# blinky_schematic.net
KiCad netlist of a schematic drawn in EAGLE
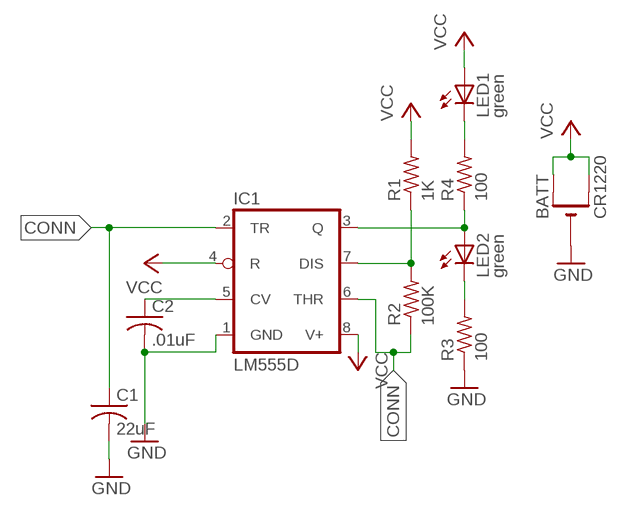
[diagram p0: schematic, sheet 1]

(export (version "E")
  (design (tool "Eeschema 10.0.6"))
  (components
    (comp (ref "BATT")
      (value "CR1220")
      (footprint "eagle-import:CR1220-SMD")
      (fields (field (name "MPN") "3080"))
      (libsource (lib "eagle-import") (part "CR1220SMT"))
    )
    (comp (ref "C1")
      (value "22uF")
      (footprint "eagle-import:C0805")
      (fields (field (name "MPN") "F981A226MSAAS1"))
      (libsource (lib "eagle-import") (part "C-USC0805"))
    )
    (comp (ref "C2")
      (value ".01uF")
      (footprint "eagle-import:C0805")
      (fields (field (name "MPN") "0805PC103KAZ1A"))
      (libsource (lib "eagle-import") (part "C-USC0805"))
    )
    (comp (ref "IC1")
      (value "LM555D")
      (footprint "eagle-import:SO08")
      (fields (field (name "MPN") "1526"))
      (libsource (lib "eagle-import") (part "555DLM"))
    )
    (comp (ref "LED1")
      (value "green")
      (footprint "eagle-import:CHIPLED_0805")
      (fields (field (name "MPN") "5988170107F"))
      (libsource (lib "eagle-import") (part "LEDCHIPLED_0805"))
    )
    (comp (ref "LED2")
      (value "green")
      (footprint "eagle-import:CHIPLED_0805")
      (fields (field (name "MPN") "5988170107F"))
      (libsource (lib "eagle-import") (part "LEDCHIPLED_0805"))
    )
    (comp (ref "R1")
      (value "1K")
      (footprint "eagle-import:R0805")
      (fields (field (name "MPN") "ERJ-6ENF1601V"))
      (libsource (lib "eagle-import") (part "R-US_R0805"))
    )
    (comp (ref "R2")
      (value "100K")
      (footprint "eagle-import:R0805")
      (fields (field (name "MF") "VISHAY/DALE") (field (name "MPN") "CRCW0805100KFKTA"))
      (libsource (lib "eagle-import") (part "R-US_R0805"))
    )
    (comp (ref "R3")
      (value "100")
      (footprint "eagle-import:R0805")
      (fields (field (name "MPN") "MCHP05W4F1000T5E"))
      (libsource (lib "eagle-import") (part "R-US_R0805"))
    )
    (comp (ref "R4")
      (value "100")
      (footprint "eagle-import:R0805")
      (fields (field (name "MPN") "MCHP05W4F1000T5E"))
      (libsource (lib "eagle-import") (part "R-US_R0805"))
    )
  )
  (nets
    (net (code "1") (name "CONN") (class "Default")
      (node (ref "C1") (pin "1") (pinfunction "1_1") (pintype "passive"))
      (node (ref "IC1") (pin "2") (pinfunction "TR_2") (pintype "input"))
      (node (ref "IC1") (pin "6") (pinfunction "THR_6") (pintype "input"))
      (node (ref "R2") (pin "1") (pinfunction "1_1") (pintype "passive"))
    )
    (net (code "2") (name "GND") (class "Default")
      (node (ref "BATT") (pin "-") (pinfunction "-_-") (pintype "passive"))
      (node (ref "C1") (pin "2") (pinfunction "2_2") (pintype "passive"))
      (node (ref "C2") (pin "2") (pinfunction "2_2") (pintype "passive"))
      (node (ref "IC1") (pin "1") (pinfunction "GND_1") (pintype "power_in"))
      (node (ref "R3") (pin "1") (pinfunction "1_1") (pintype "passive"))
    )
    (net (code "3") (name "Net-(IC1-CV)") (class "Default")
      (node (ref "C2") (pin "1") (pinfunction "1_1") (pintype "passive"))
      (node (ref "IC1") (pin "5") (pinfunction "CV_5") (pintype "input"))
    )
    (net (code "4") (name "Net-(IC1-DIS)") (class "Default")
      (node (ref "IC1") (pin "7") (pinfunction "DIS_7") (pintype "input"))
      (node (ref "R1") (pin "1") (pinfunction "1_1") (pintype "passive"))
      (node (ref "R2") (pin "2") (pinfunction "2_2") (pintype "passive"))
    )
    (net (code "5") (name "Net-(IC1-Q)") (class "Default")
      (node (ref "IC1") (pin "3") (pinfunction "Q_3") (pintype "output"))
      (node (ref "LED2") (pin "A") (pinfunction "A_A") (pintype "passive"))
      (node (ref "R4") (pin "1") (pinfunction "1_1") (pintype "passive"))
    )
    (net (code "6") (name "Net-(LED1-PadC)") (class "Default")
      (node (ref "LED1") (pin "C") (pinfunction "C_C") (pintype "passive"))
      (node (ref "R4") (pin "2") (pinfunction "2_2") (pintype "passive"))
    )
    (net (code "7") (name "Net-(LED2-PadC)") (class "Default")
      (node (ref "LED2") (pin "C") (pinfunction "C_C") (pintype "passive"))
      (node (ref "R3") (pin "2") (pinfunction "2_2") (pintype "passive"))
    )
    (net (code "8") (name "VCC") (class "Default")
      (node (ref "BATT") (pin "+$1") (pinfunction "+_+$1") (pintype "passive"))
      (node (ref "BATT") (pin "+$2") (pinfunction "+1_+$2") (pintype "passive"))
      (node (ref "IC1") (pin "4") (pinfunction "R_4") (pintype "input"))
      (node (ref "IC1") (pin "8") (pinfunction "V+_8") (pintype "power_in"))
      (node (ref "LED1") (pin "A") (pinfunction "A_A") (pintype "passive"))
      (node (ref "R1") (pin "2") (pinfunction "2_2") (pintype "passive"))
    )
  )
)
